# ShieldDuckSensor.net
KiCad netlist of a schematic drawn in EAGLE
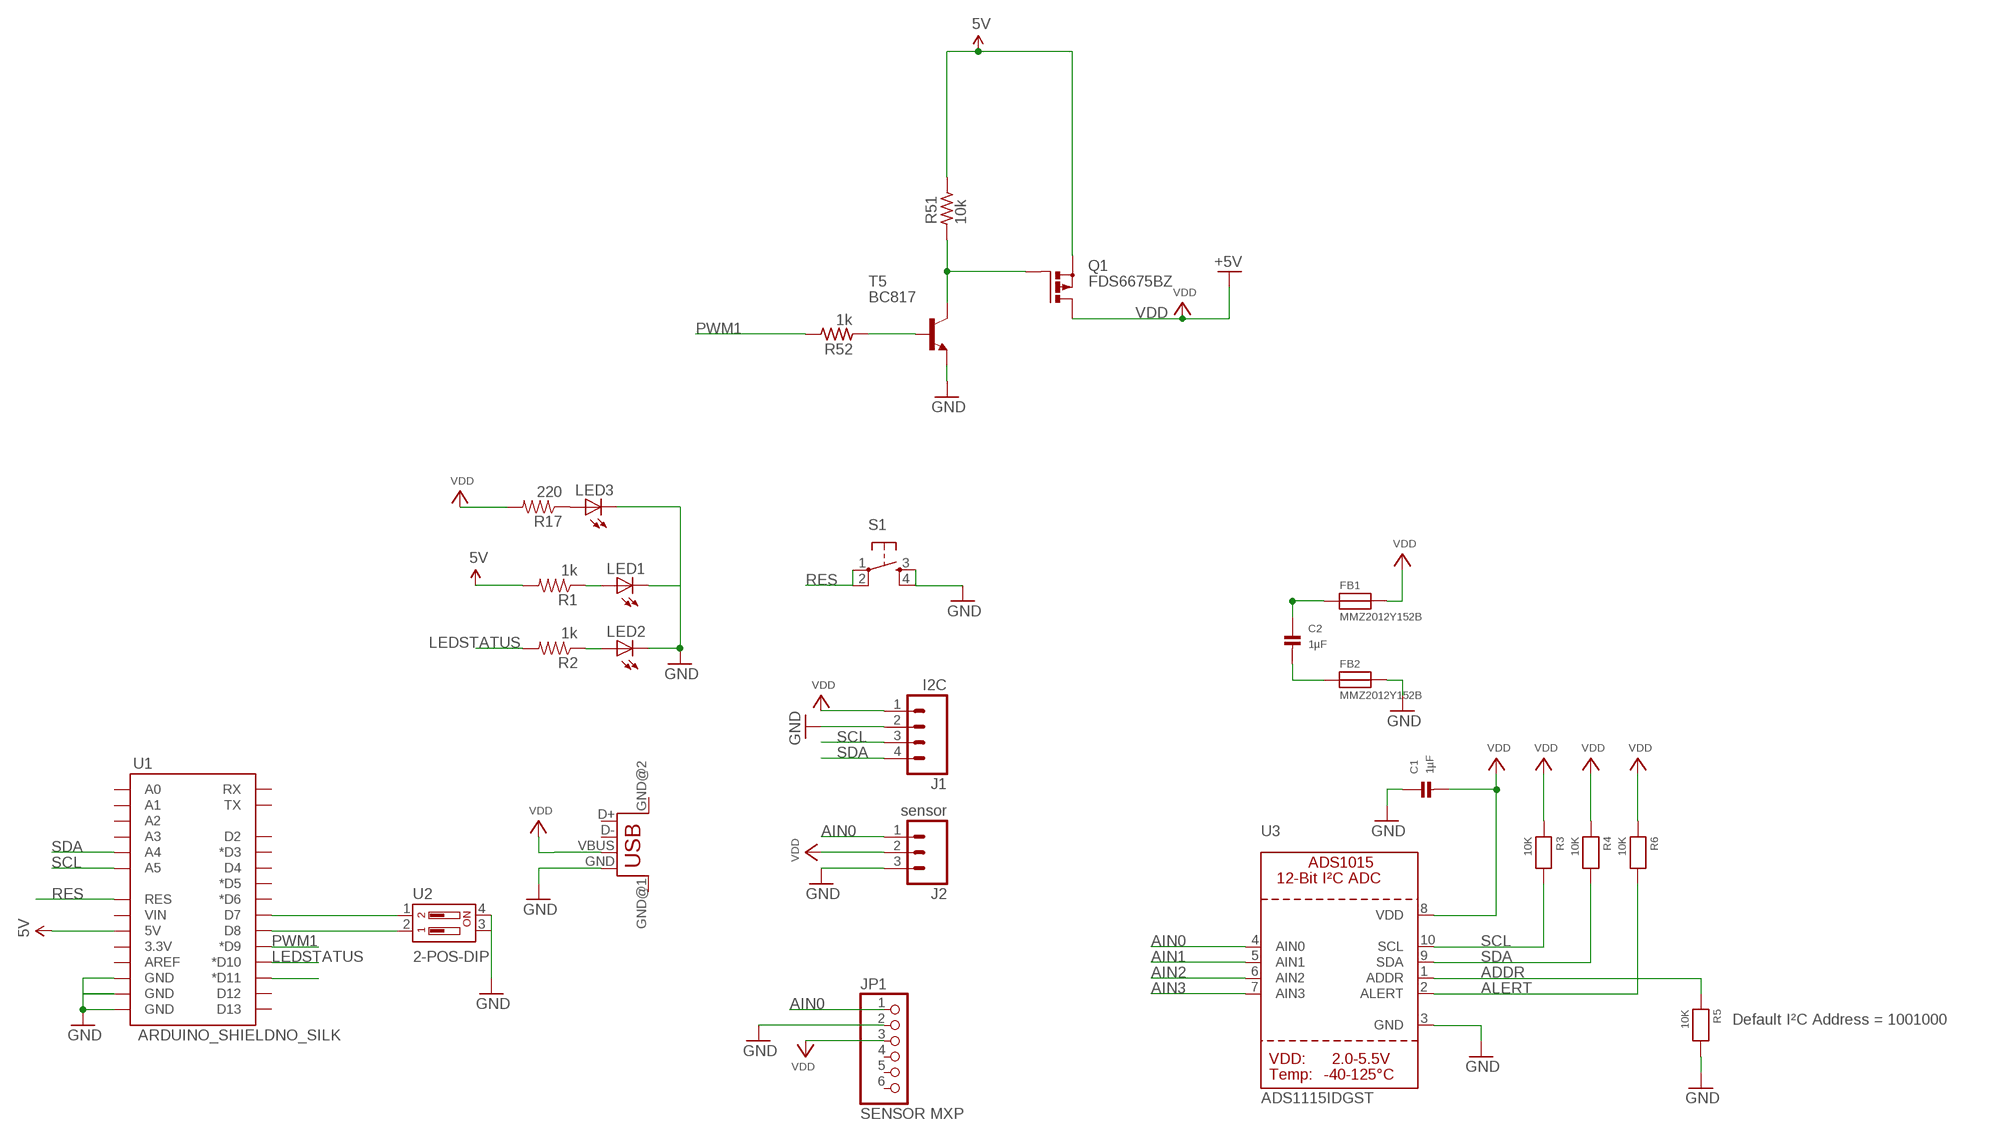
[diagram p0: schematic, sheet 1]

(export (version "E")
  (design (tool "Eeschema 10.0.6"))
  (components
    (comp (ref "C1")
      (value "1µF")
      (footprint "eagle-import:0805")
      (libsource (lib "eagle-import") (part "CAP_CERAMIC0805"))
    )
    (comp (ref "C2")
      (value "1µF")
      (footprint "eagle-import:0805")
      (libsource (lib "eagle-import") (part "CAP_CERAMIC0805"))
    )
    (comp (ref "FB1")
      (value "MMZ2012Y152B")
      (footprint "eagle-import:0805")
      (libsource (lib "eagle-import") (part "FERRITE0805"))
    )
    (comp (ref "FB2")
      (value "MMZ2012Y152B")
      (footprint "eagle-import:0805")
      (libsource (lib "eagle-import") (part "FERRITE0805"))
    )
    (comp (ref "J1")
      (value "I2C")
      (footprint "eagle-import:1X04")
      (libsource (lib "eagle-import") (part "M04PTH"))
    )
    (comp (ref "J2")
      (value "sensor")
      (footprint "eagle-import:1X03")
      (libsource (lib "eagle-import") (part "M03PTH"))
    )
    (comp (ref "JP1")
      (value "SENSOR MXP")
      (footprint "eagle-import:1X06-BIG")
      (libsource (lib "eagle-import") (part "PINHD-1X6B"))
    )
    (comp (ref "LED1")
      (value "LED3MM")
      (footprint "eagle-import:LED3MM")
      (libsource (lib "eagle-import") (part "LED3MM"))
    )
    (comp (ref "LED2")
      (value "LED3MM")
      (footprint "eagle-import:LED3MM")
      (libsource (lib "eagle-import") (part "LED3MM"))
    )
    (comp (ref "LED3")
      (value "LED3MM")
      (footprint "eagle-import:LED3MM")
      (libsource (lib "eagle-import") (part "LED3MM"))
    )
    (comp (ref "Q1")
      (value "FDS6675BZ")
      (footprint "eagle-import:SO-08")
      (libsource (lib "eagle-import") (part "P-MOSFET-SO8"))
    )
    (comp (ref "R1")
      (value "1k")
      (footprint "eagle-import:0805")
      (libsource (lib "eagle-import") (part "RESISTOR0805-RES"))
    )
    (comp (ref "R2")
      (value "1k")
      (footprint "eagle-import:0805")
      (libsource (lib "eagle-import") (part "RESISTOR0805-RES"))
    )
    (comp (ref "R3")
      (value "10K")
      (footprint "eagle-import:0805")
      (libsource (lib "eagle-import") (part "RESISTOR0805"))
    )
    (comp (ref "R4")
      (value "10K")
      (footprint "eagle-import:0805")
      (libsource (lib "eagle-import") (part "RESISTOR0805"))
    )
    (comp (ref "R5")
      (value "10K")
      (footprint "eagle-import:0805")
      (libsource (lib "eagle-import") (part "RESISTOR0805"))
    )
    (comp (ref "R6")
      (value "10K")
      (footprint "eagle-import:0805")
      (libsource (lib "eagle-import") (part "RESISTOR0805"))
    )
    (comp (ref "R17")
      (value "220")
      (footprint "eagle-import:0805")
      (libsource (lib "eagle-import") (part "RESISTOR0805-RES"))
    )
    (comp (ref "R51")
      (value "10k")
      (footprint "eagle-import:R0805")
      (libsource (lib "eagle-import") (part "R_0805"))
    )
    (comp (ref "R52")
      (value "1k")
      (footprint "eagle-import:R0805")
      (libsource (lib "eagle-import") (part "R_0805"))
    )
    (comp (ref "S1")
      (value "TAC_SWITCHPTH")
      (footprint "eagle-import:TACTILE-PTH")
      (libsource (lib "eagle-import") (part "TAC_SWITCHPTH"))
    )
    (comp (ref "T5")
      (value "BC817")
      (footprint "eagle-import:SOT23-BEC")
      (libsource (lib "eagle-import") (part "-NPN-SOT23-BECBC817-16LT1"))
    )
    (comp (ref "U$1")
      (value "USB")
      (footprint "eagle-import:USB-FEMALE-A-PTH")
      (libsource (lib "eagle-import") (part "USB"))
    )
    (comp (ref "U1")
      (value "ARDUINO_SHIELDNO_SILK")
      (footprint "eagle-import:DUEMILANOVE_VIAS")
      (libsource (lib "eagle-import") (part "ARDUINO_SHIELDNO_SILK"))
    )
    (comp (ref "U2")
      (value "2-POS-DIP")
      (footprint "eagle-import:209-2LPST")
      (libsource (lib "eagle-import") (part "2-POS-DIPCTS-THRU-HOLE"))
    )
    (comp (ref "U3")
      (value "ADS1115IDGST")
      (footprint "eagle-import:MSOP10")
      (libsource (lib "eagle-import") (part "ADC_ADS1015"))
    )
  )
  (nets
    (net (code "1") (name "+5V") (class "Default")
      (node (ref "C1") (pin "2") (pinfunction "P$2_2") (pintype "passive"))
      (node (ref "FB1") (pin "2") (pinfunction "P$2_2") (pintype "bidirectional"))
      (node (ref "J1") (pin "1") (pinfunction "1_1") (pintype "passive"))
      (node (ref "J2") (pin "2") (pinfunction "2_2") (pintype "passive"))
      (node (ref "JP1") (pin "3") (pinfunction "3_3") (pintype "passive"))
      (node (ref "Q1") (pin "5") (pinfunction "D_5") (pintype "passive"))
      (node (ref "Q1") (pin "6") (pinfunction "D_6") (pintype "passive"))
      (node (ref "Q1") (pin "7") (pinfunction "D_7") (pintype "passive"))
      (node (ref "Q1") (pin "8") (pinfunction "D_8") (pintype "passive"))
      (node (ref "R17") (pin "2") (pinfunction "2_2") (pintype "passive"))
      (node (ref "R3") (pin "1") (pinfunction "1_1") (pintype "passive"))
      (node (ref "R4") (pin "1") (pinfunction "1_1") (pintype "passive"))
      (node (ref "R6") (pin "1") (pinfunction "1_1") (pintype "passive"))
      (node (ref "U$1") (pin "VBUS") (pinfunction "VBUS_VBUS") (pintype "bidirectional"))
      (node (ref "U3") (pin "8") (pinfunction "VDD_8") (pintype "bidirectional"))
    )
    (net (code "2") (name "/ADDR") (class "Default")
      (node (ref "R5") (pin "1") (pinfunction "1_1") (pintype "passive"))
      (node (ref "U3") (pin "1") (pinfunction "ADDR_1") (pintype "bidirectional"))
    )
    (net (code "3") (name "/AIN0") (class "Default")
      (node (ref "J2") (pin "1") (pinfunction "1_1") (pintype "passive"))
      (node (ref "JP1") (pin "1") (pinfunction "1_1") (pintype "passive"))
      (node (ref "U3") (pin "4") (pinfunction "AIN0_4") (pintype "bidirectional"))
    )
    (net (code "4") (name "/AIN1") (class "Default")
      (node (ref "U3") (pin "5") (pinfunction "AIN1_5") (pintype "bidirectional"))
    )
    (net (code "5") (name "/AIN2") (class "Default")
      (node (ref "U3") (pin "6") (pinfunction "AIN2_6") (pintype "bidirectional"))
    )
    (net (code "6") (name "/AIN3") (class "Default")
      (node (ref "U3") (pin "7") (pinfunction "AIN3_7") (pintype "bidirectional"))
    )
    (net (code "7") (name "/ALERT") (class "Default")
      (node (ref "R6") (pin "2") (pinfunction "2_2") (pintype "passive"))
      (node (ref "U3") (pin "2") (pinfunction "ALERT_2") (pintype "bidirectional"))
    )
    (net (code "8") (name "/LEDSTATUS") (class "Default")
      (node (ref "R2") (pin "2") (pinfunction "2_2") (pintype "passive"))
      (node (ref "U1") (pin "D10") (pinfunction "*D10_D10") (pintype "bidirectional"))
    )
    (net (code "9") (name "/PWM1") (class "Default")
      (node (ref "R52") (pin "2") (pinfunction "2_2") (pintype "passive"))
      (node (ref "U1") (pin "D9") (pinfunction "*D9_D9") (pintype "bidirectional"))
    )
    (net (code "10") (name "/RES") (class "Default")
      (node (ref "S1") (pin "1") (pinfunction "1_1") (pintype "passive"))
      (node (ref "S1") (pin "2") (pinfunction "2_2") (pintype "passive"))
      (node (ref "U1") (pin "RES") (pinfunction "RES_RES") (pintype "bidirectional"))
    )
    (net (code "11") (name "/SCL") (class "Default")
      (node (ref "J1") (pin "3") (pinfunction "3_3") (pintype "passive"))
      (node (ref "R3") (pin "2") (pinfunction "2_2") (pintype "passive"))
      (node (ref "U1") (pin "A5") (pinfunction "A5_A5") (pintype "bidirectional"))
      (node (ref "U3") (pin "10") (pinfunction "SCL_10") (pintype "bidirectional"))
    )
    (net (code "12") (name "/SDA") (class "Default")
      (node (ref "J1") (pin "4") (pinfunction "4_4") (pintype "passive"))
      (node (ref "R4") (pin "2") (pinfunction "2_2") (pintype "passive"))
      (node (ref "U1") (pin "A4") (pinfunction "A4_A4") (pintype "bidirectional"))
      (node (ref "U3") (pin "9") (pinfunction "SDA_9") (pintype "bidirectional"))
    )
    (net (code "13") (name "5V") (class "Default")
      (node (ref "Q1") (pin "1") (pinfunction "S_1") (pintype "passive"))
      (node (ref "Q1") (pin "2") (pinfunction "S_2") (pintype "passive"))
      (node (ref "Q1") (pin "3") (pinfunction "S_3") (pintype "passive"))
      (node (ref "R1") (pin "2") (pinfunction "2_2") (pintype "passive"))
      (node (ref "R51") (pin "2") (pinfunction "2_2") (pintype "passive"))
      (node (ref "U1") (pin "5V") (pinfunction "5V_5V") (pintype "bidirectional"))
    )
    (net (code "14") (name "GND") (class "Default")
      (node (ref "C1") (pin "1") (pinfunction "P$1_1") (pintype "passive"))
      (node (ref "FB2") (pin "2") (pinfunction "P$2_2") (pintype "bidirectional"))
      (node (ref "J1") (pin "2") (pinfunction "2_2") (pintype "passive"))
      (node (ref "J2") (pin "3") (pinfunction "3_3") (pintype "passive"))
      (node (ref "JP1") (pin "2") (pinfunction "2_2") (pintype "passive"))
      (node (ref "LED1") (pin "K") (pinfunction "C_K") (pintype "passive"))
      (node (ref "LED2") (pin "K") (pinfunction "C_K") (pintype "passive"))
      (node (ref "LED3") (pin "K") (pinfunction "C_K") (pintype "passive"))
      (node (ref "R5") (pin "2") (pinfunction "2_2") (pintype "passive"))
      (node (ref "S1") (pin "3") (pinfunction "3_3") (pintype "passive"))
      (node (ref "S1") (pin "4") (pinfunction "4_4") (pintype "passive"))
      (node (ref "T5") (pin "E") (pinfunction "E_E") (pintype "passive"))
      (node (ref "U$1") (pin "GND") (pinfunction "GND_GND") (pintype "bidirectional"))
      (node (ref "U1") (pin "GND@0") (pinfunction "GND_GND@0") (pintype "bidirectional"))
      (node (ref "U1") (pin "GND@1") (pinfunction "GND_GND@1") (pintype "bidirectional"))
      (node (ref "U1") (pin "GND@2") (pinfunction "GND_GND@2") (pintype "bidirectional"))
      (node (ref "U2") (pin "3") (pinfunction "P$3_3") (pintype "bidirectional"))
      (node (ref "U2") (pin "4") (pinfunction "P$4_4") (pintype "bidirectional"))
      (node (ref "U3") (pin "3") (pinfunction "GND_3") (pintype "bidirectional"))
    )
    (net (code "15") (name "Net-(C2-P$1)") (class "Default")
      (node (ref "C2") (pin "1") (pinfunction "P$1_1") (pintype "passive"))
      (node (ref "FB1") (pin "1") (pinfunction "P$1_1") (pintype "bidirectional"))
    )
    (net (code "16") (name "Net-(C2-P$2)") (class "Default")
      (node (ref "C2") (pin "2") (pinfunction "P$2_2") (pintype "passive"))
      (node (ref "FB2") (pin "1") (pinfunction "P$1_1") (pintype "bidirectional"))
    )
    (net (code "17") (name "Net-(LED1-PadA)") (class "Default")
      (node (ref "LED1") (pin "A") (pinfunction "A_A") (pintype "passive"))
      (node (ref "R1") (pin "1") (pinfunction "1_1") (pintype "passive"))
    )
    (net (code "18") (name "Net-(LED2-PadA)") (class "Default")
      (node (ref "LED2") (pin "A") (pinfunction "A_A") (pintype "passive"))
      (node (ref "R2") (pin "1") (pinfunction "1_1") (pintype "passive"))
    )
    (net (code "19") (name "Net-(LED3-PadA)") (class "Default")
      (node (ref "LED3") (pin "A") (pinfunction "A_A") (pintype "passive"))
      (node (ref "R17") (pin "1") (pinfunction "1_1") (pintype "passive"))
    )
    (net (code "20") (name "Net-(Q1-G)") (class "Default")
      (node (ref "Q1") (pin "4") (pinfunction "G_4") (pintype "passive"))
      (node (ref "R51") (pin "1") (pinfunction "1_1") (pintype "passive"))
      (node (ref "T5") (pin "C") (pinfunction "C_C") (pintype "passive"))
    )
    (net (code "21") (name "Net-(R52-Pad1)") (class "Default")
      (node (ref "R52") (pin "1") (pinfunction "1_1") (pintype "passive"))
      (node (ref "T5") (pin "B") (pinfunction "B_B") (pintype "passive"))
    )
    (net (code "22") (name "Net-(U2-P$1)") (class "Default")
      (node (ref "U1") (pin "D7") (pinfunction "D7_D7") (pintype "bidirectional"))
      (node (ref "U2") (pin "1") (pinfunction "P$1_1") (pintype "bidirectional"))
    )
    (net (code "23") (name "Net-(U2-P$2)") (class "Default")
      (node (ref "U1") (pin "D8") (pinfunction "D8_D8") (pintype "bidirectional"))
      (node (ref "U2") (pin "2") (pinfunction "P$2_2") (pintype "bidirectional"))
    )
    (net (code "24") (name "unconnected-(JP1-Pad4)") (class "Default")
      (node (ref "JP1") (pin "4") (pinfunction "4_4") (pintype "passive"))
    )
    (net (code "25") (name "unconnected-(JP1-Pad5)") (class "Default")
      (node (ref "JP1") (pin "5") (pinfunction "5_5") (pintype "passive"))
    )
    (net (code "26") (name "unconnected-(JP1-Pad6)") (class "Default")
      (node (ref "JP1") (pin "6") (pinfunction "6_6") (pintype "passive"))
    )
    (net (code "27") (name "unconnected-(U$1-GND-PadGND@1)") (class "Default")
      (node (ref "U$1") (pin "GND@1") (pinfunction "GND_GND@1") (pintype "bidirectional"))
    )
    (net (code "28") (name "unconnected-(U$1-GND-PadGND@2)") (class "Default")
      (node (ref "U$1") (pin "GND@2") (pinfunction "GND_GND@2") (pintype "bidirectional"))
    )
    (net (code "29") (name "unconnected-(U$1-PadD+)") (class "Default")
      (node (ref "U$1") (pin "D+") (pinfunction "D+_D+") (pintype "bidirectional"))
    )
    (net (code "30") (name "unconnected-(U$1-PadD-)") (class "Default")
      (node (ref "U$1") (pin "D-") (pinfunction "D-_D-") (pintype "bidirectional"))
    )
    (net (code "31") (name "unconnected-(U1-*D3-PadD3)") (class "Default")
      (node (ref "U1") (pin "D3") (pinfunction "*D3_D3") (pintype "bidirectional"))
    )
    (net (code "32") (name "unconnected-(U1-*D5-PadD5)") (class "Default")
      (node (ref "U1") (pin "D5") (pinfunction "*D5_D5") (pintype "bidirectional"))
    )
    (net (code "33") (name "unconnected-(U1-*D6-PadD6)") (class "Default")
      (node (ref "U1") (pin "D6") (pinfunction "*D6_D6") (pintype "bidirectional"))
    )
    (net (code "34") (name "unconnected-(U1-*D11-PadD11)") (class "Default")
      (node (ref "U1") (pin "D11") (pinfunction "*D11_D11") (pintype "bidirectional"))
    )
    (net (code "35") (name "unconnected-(U1-Pad3.3V)") (class "Default")
      (node (ref "U1") (pin "3.3V") (pinfunction "3.3V_3.3V") (pintype "bidirectional"))
    )
    (net (code "36") (name "unconnected-(U1-PadA0)") (class "Default")
      (node (ref "U1") (pin "A0") (pinfunction "A0_A0") (pintype "bidirectional"))
    )
    (net (code "37") (name "unconnected-(U1-PadA1)") (class "Default")
      (node (ref "U1") (pin "A1") (pinfunction "A1_A1") (pintype "bidirectional"))
    )
    (net (code "38") (name "unconnected-(U1-PadA2)") (class "Default")
      (node (ref "U1") (pin "A2") (pinfunction "A2_A2") (pintype "bidirectional"))
    )
    (net (code "39") (name "unconnected-(U1-PadA3)") (class "Default")
      (node (ref "U1") (pin "A3") (pinfunction "A3_A3") (pintype "bidirectional"))
    )
    (net (code "40") (name "unconnected-(U1-PadAREF)") (class "Default")
      (node (ref "U1") (pin "AREF") (pinfunction "AREF_AREF") (pintype "bidirectional"))
    )
    (net (code "41") (name "unconnected-(U1-PadD2)") (class "Default")
      (node (ref "U1") (pin "D2") (pinfunction "D2_D2") (pintype "bidirectional"))
    )
    (net (code "42") (name "unconnected-(U1-PadD4)") (class "Default")
      (node (ref "U1") (pin "D4") (pinfunction "D4_D4") (pintype "bidirectional"))
    )
    (net (code "43") (name "unconnected-(U1-PadD12)") (class "Default")
      (node (ref "U1") (pin "D12") (pinfunction "D12_D12") (pintype "bidirectional"))
    )
    (net (code "44") (name "unconnected-(U1-PadD13)") (class "Default")
      (node (ref "U1") (pin "D13") (pinfunction "D13_D13") (pintype "bidirectional"))
    )
    (net (code "45") (name "unconnected-(U1-PadRX)") (class "Default")
      (node (ref "U1") (pin "RX") (pinfunction "RX_RX") (pintype "bidirectional"))
    )
    (net (code "46") (name "unconnected-(U1-PadTX)") (class "Default")
      (node (ref "U1") (pin "TX") (pinfunction "TX_TX") (pintype "bidirectional"))
    )
    (net (code "47") (name "unconnected-(U1-PadVIN)") (class "Default")
      (node (ref "U1") (pin "VIN") (pinfunction "VIN_VIN") (pintype "bidirectional"))
    )
  )
)
